# MiniDuino-v2.net
KiCad netlist of a schematic drawn in EAGLE
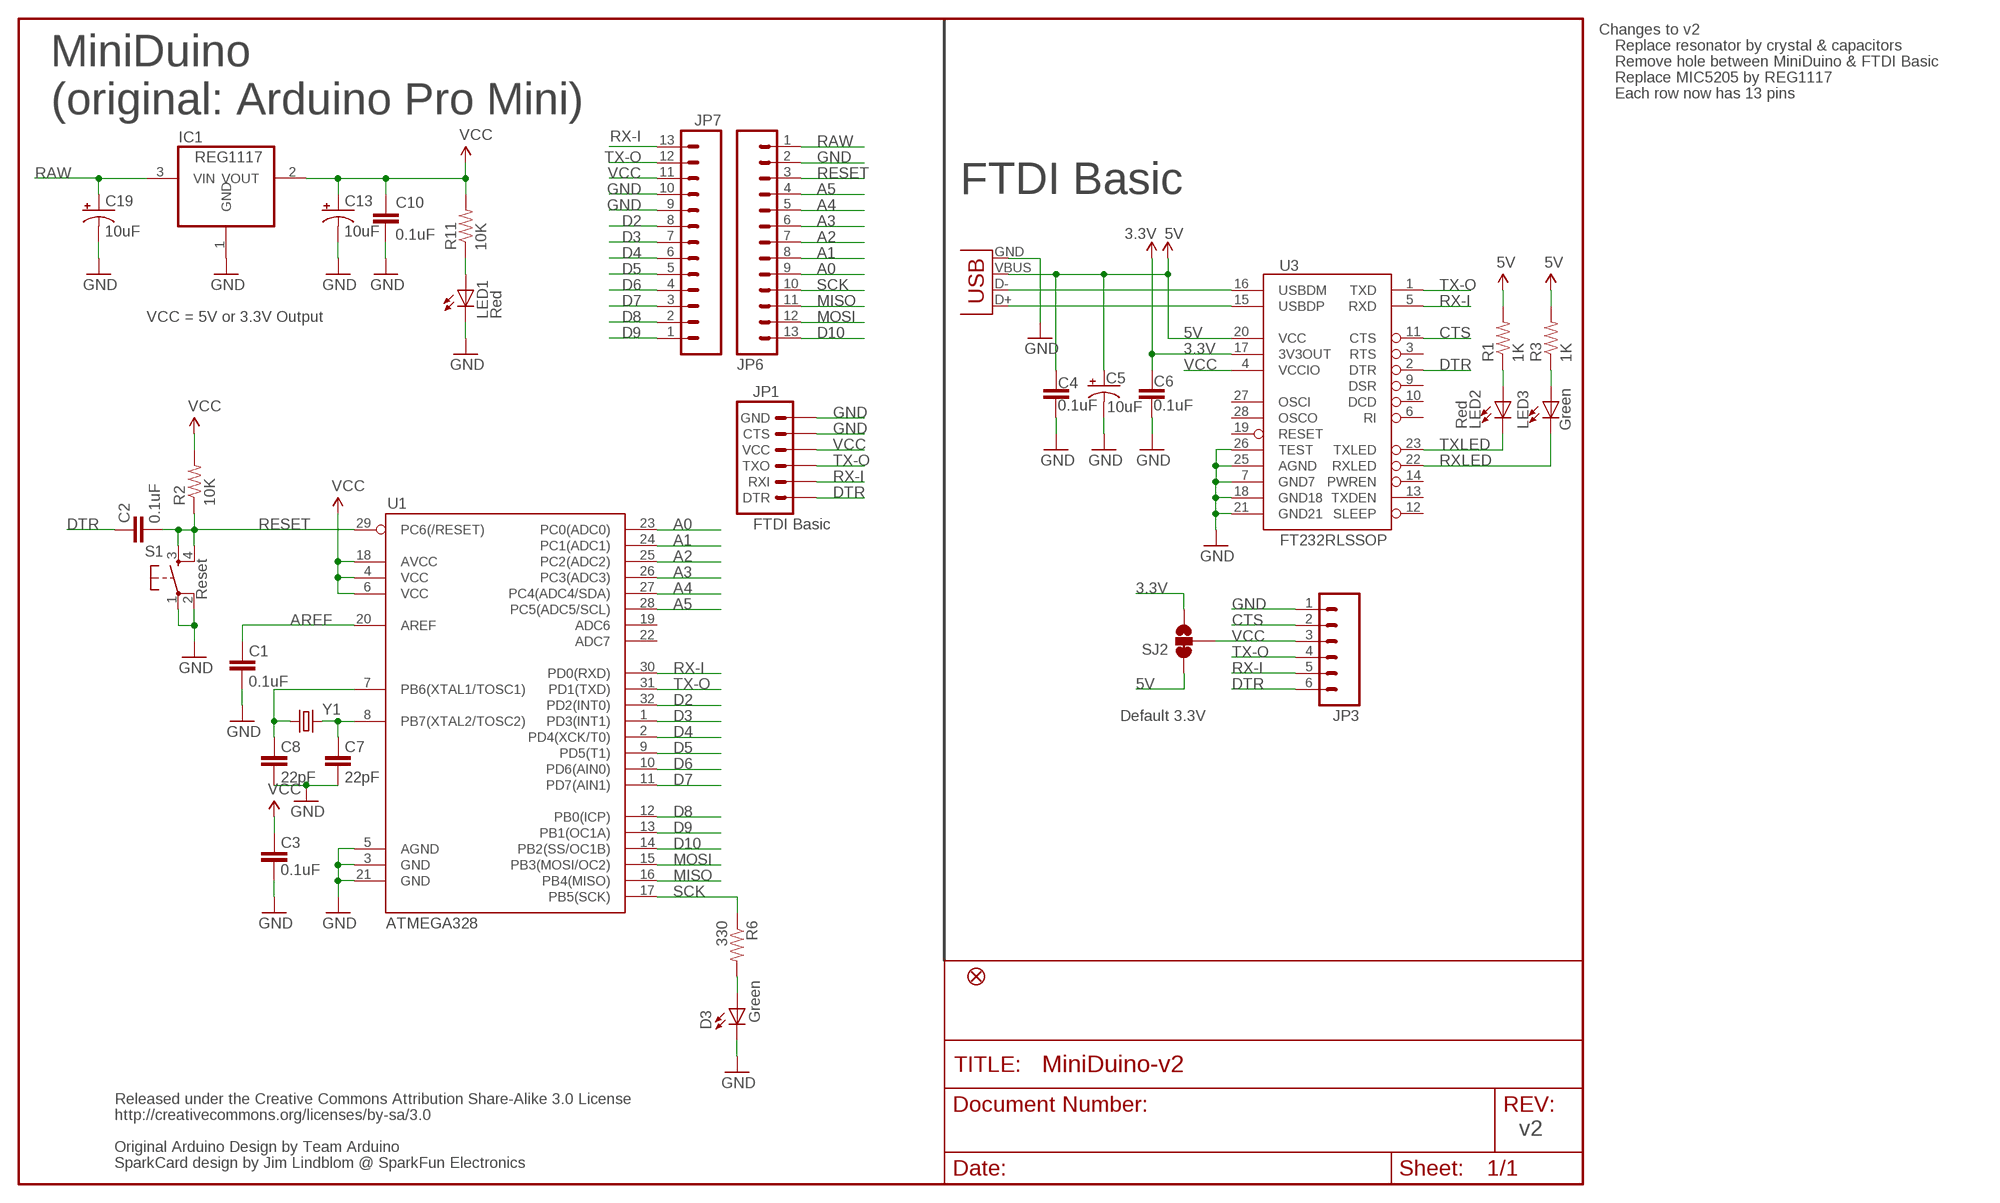
[diagram p0: schematic, sheet 1]

(export (version "E")
  (design (tool "Eeschema 10.0.6"))
  (components
    (comp (ref "C1")
      (value "0.1uF")
      (footprint "eagle-import:0402-CAP")
      (libsource (lib "eagle-import") (part "CAP0402-CAP"))
    )
    (comp (ref "C2")
      (value "0.1uF")
      (footprint "eagle-import:0402-CAP")
      (libsource (lib "eagle-import") (part "CAP0402-CAP"))
    )
    (comp (ref "C3")
      (value "0.1uF")
      (footprint "eagle-import:0402-CAP")
      (libsource (lib "eagle-import") (part "CAP0402-CAP"))
    )
    (comp (ref "C4")
      (value "0.1uF")
      (footprint "eagle-import:0402-CAP")
      (libsource (lib "eagle-import") (part "CAP0402-CAP"))
    )
    (comp (ref "C5")
      (value "10uF")
      (footprint "eagle-import:EIA3216")
      (libsource (lib "eagle-import") (part "CAP_POL1206"))
    )
    (comp (ref "C6")
      (value "0.1uF")
      (footprint "eagle-import:0402-CAP")
      (libsource (lib "eagle-import") (part "CAP0402-CAP"))
    )
    (comp (ref "C7")
      (value "22pF")
      (footprint "eagle-import:0402-CAP")
      (libsource (lib "eagle-import") (part "CAP0402-CAP"))
    )
    (comp (ref "C8")
      (value "22pF")
      (footprint "eagle-import:0402-CAP")
      (libsource (lib "eagle-import") (part "CAP0402-CAP"))
    )
    (comp (ref "C10")
      (value "0.1uF")
      (footprint "eagle-import:0402-CAP")
      (libsource (lib "eagle-import") (part "CAP0402-CAP"))
    )
    (comp (ref "C13")
      (value "10uF")
      (footprint "eagle-import:EIA3216")
      (libsource (lib "eagle-import") (part "CAP_POL1206"))
    )
    (comp (ref "C19")
      (value "10uF")
      (footprint "eagle-import:EIA3216")
      (libsource (lib "eagle-import") (part "CAP_POL1206"))
    )
    (comp (ref "D3")
      (value "Green")
      (footprint "eagle-import:LED-0603")
      (libsource (lib "eagle-import") (part "LED0603"))
    )
    (comp (ref "IC1")
      (value "REG1117")
      (footprint "eagle-import:SOT223")
      (libsource (lib "eagle-import") (part "REG1117"))
    )
    (comp (ref "JP1")
      (value "FTDI Basic")
      (footprint "eagle-import:1X06")
      (libsource (lib "eagle-import") (part "ARDUINO_SERIAL_PROGRAMPTH"))
    )
    (comp (ref "JP3")
      (value "M06SIP")
      (footprint "eagle-import:1X06")
      (libsource (lib "eagle-import") (part "M06SIP"))
    )
    (comp (ref "JP6")
      (value "M13")
      (footprint "eagle-import:1X13")
      (libsource (lib "eagle-import") (part "M13"))
    )
    (comp (ref "JP7")
      (value "M13")
      (footprint "eagle-import:1X13")
      (libsource (lib "eagle-import") (part "M13"))
    )
    (comp (ref "JP16")
      (value "FIDUCIAL1X2.5")
      (footprint "eagle-import:FIDUCIAL-1X2.5")
      (libsource (lib "eagle-import") (part "FIDUCIAL1X2.5"))
    )
    (comp (ref "LED1")
      (value "Red")
      (footprint "eagle-import:LED-0603")
      (libsource (lib "eagle-import") (part "LED0603"))
    )
    (comp (ref "LED2")
      (value "Red")
      (footprint "eagle-import:LED-0603")
      (libsource (lib "eagle-import") (part "LED0603"))
    )
    (comp (ref "LED3")
      (value "Green")
      (footprint "eagle-import:LED-0603")
      (libsource (lib "eagle-import") (part "LED0603"))
    )
    (comp (ref "R1")
      (value "1K")
      (footprint "eagle-import:0603-RES")
      (libsource (lib "eagle-import") (part "RESISTOR0603-RES"))
    )
    (comp (ref "R2")
      (value "10K")
      (footprint "eagle-import:0402-RES")
      (libsource (lib "eagle-import") (part "RESISTOR0402-RES"))
    )
    (comp (ref "R3")
      (value "1K")
      (footprint "eagle-import:0603-RES")
      (libsource (lib "eagle-import") (part "RESISTOR0603-RES"))
    )
    (comp (ref "R6")
      (value "330")
      (footprint "eagle-import:0402-RES")
      (libsource (lib "eagle-import") (part "RESISTOR0402-RES"))
    )
    (comp (ref "R11")
      (value "10K")
      (footprint "eagle-import:0402-RES")
      (libsource (lib "eagle-import") (part "RESISTOR0402-RES"))
    )
    (comp (ref "S1")
      (value "Reset")
      (footprint "eagle-import:TACTILE_SWITCH_SMD")
      (libsource (lib "eagle-import") (part "TAC_SWITCHSMD"))
    )
    (comp (ref "SJ2")
      (value "SOLDERJUMPER_2WAYS")
      (footprint "eagle-import:SJ_3")
      (libsource (lib "eagle-import") (part "SOLDERJUMPER_2WAYS"))
    )
    (comp (ref "U1")
      (value "ATMEGA328")
      (footprint "eagle-import:TQFP32-08")
      (libsource (lib "eagle-import") (part "ATMEGA168"))
    )
    (comp (ref "U3")
      (value "FT232RLSSOP")
      (footprint "eagle-import:SSOP28DB")
      (libsource (lib "eagle-import") (part "FT232RLSSOP"))
    )
    (comp (ref "X2")
      (value "USB-SMD-NS")
      (footprint "eagle-import:USB-MINIB-NOSTOP")
      (libsource (lib "eagle-import") (part "USB-SMD-NS"))
    )
    (comp (ref "Y1")
      (value "CRYSTAL5X3")
      (footprint "eagle-import:CRYSTAL-SMD-5X3")
      (libsource (lib "eagle-import") (part "CRYSTAL5X3"))
    )
  )
  (nets
    (net (code "1") (name "/A0") (class "Default")
      (node (ref "JP6") (pin "9") (pinfunction "9_9") (pintype "passive"))
      (node (ref "U1") (pin "23") (pinfunction "PC0(ADC0)_23") (pintype "bidirectional"))
    )
    (net (code "2") (name "/A1") (class "Default")
      (node (ref "JP6") (pin "8") (pinfunction "8_8") (pintype "passive"))
      (node (ref "U1") (pin "24") (pinfunction "PC1(ADC1)_24") (pintype "bidirectional"))
    )
    (net (code "3") (name "/A2") (class "Default")
      (node (ref "JP6") (pin "7") (pinfunction "7_7") (pintype "passive"))
      (node (ref "U1") (pin "25") (pinfunction "PC2(ADC2)_25") (pintype "bidirectional"))
    )
    (net (code "4") (name "/A3") (class "Default")
      (node (ref "JP6") (pin "6") (pinfunction "6_6") (pintype "passive"))
      (node (ref "U1") (pin "26") (pinfunction "PC3(ADC3)_26") (pintype "bidirectional"))
    )
    (net (code "5") (name "/A4") (class "Default")
      (node (ref "JP6") (pin "5") (pinfunction "5_5") (pintype "passive"))
      (node (ref "U1") (pin "27") (pinfunction "PC4(ADC4/SDA)_27") (pintype "bidirectional"))
    )
    (net (code "6") (name "/A5") (class "Default")
      (node (ref "JP6") (pin "4") (pinfunction "4_4") (pintype "passive"))
      (node (ref "U1") (pin "28") (pinfunction "PC5(ADC5/SCL)_28") (pintype "bidirectional"))
    )
    (net (code "7") (name "/AREF") (class "Default")
      (node (ref "C1") (pin "2") (pinfunction "2_2") (pintype "passive"))
      (node (ref "U1") (pin "20") (pinfunction "AREF_20") (pintype "bidirectional"))
    )
    (net (code "8") (name "/CTS") (class "Default")
      (node (ref "JP3") (pin "2") (pinfunction "2_2") (pintype "passive"))
      (node (ref "U3") (pin "11") (pinfunction "CTS_11") (pintype "input"))
    )
    (net (code "9") (name "/D2") (class "Default")
      (node (ref "JP7") (pin "8") (pinfunction "8_8") (pintype "passive"))
      (node (ref "U1") (pin "32") (pinfunction "PD2(INT0)_32") (pintype "bidirectional"))
    )
    (net (code "10") (name "/D3") (class "Default")
      (node (ref "JP7") (pin "7") (pinfunction "7_7") (pintype "passive"))
      (node (ref "U1") (pin "1") (pinfunction "PD3(INT1)_1") (pintype "bidirectional"))
    )
    (net (code "11") (name "/D4") (class "Default")
      (node (ref "JP7") (pin "6") (pinfunction "6_6") (pintype "passive"))
      (node (ref "U1") (pin "2") (pinfunction "PD4(XCK/T0)_2") (pintype "bidirectional"))
    )
    (net (code "12") (name "/D5") (class "Default")
      (node (ref "JP7") (pin "5") (pinfunction "5_5") (pintype "passive"))
      (node (ref "U1") (pin "9") (pinfunction "PD5(T1)_9") (pintype "bidirectional"))
    )
    (net (code "13") (name "/D6") (class "Default")
      (node (ref "JP7") (pin "4") (pinfunction "4_4") (pintype "passive"))
      (node (ref "U1") (pin "10") (pinfunction "PD6(AIN0)_10") (pintype "bidirectional"))
    )
    (net (code "14") (name "/D7") (class "Default")
      (node (ref "JP7") (pin "3") (pinfunction "3_3") (pintype "passive"))
      (node (ref "U1") (pin "11") (pinfunction "PD7(AIN1)_11") (pintype "bidirectional"))
    )
    (net (code "15") (name "/D8") (class "Default")
      (node (ref "JP7") (pin "2") (pinfunction "2_2") (pintype "passive"))
      (node (ref "U1") (pin "12") (pinfunction "PB0(ICP)_12") (pintype "bidirectional"))
    )
    (net (code "16") (name "/D9") (class "Default")
      (node (ref "JP7") (pin "1") (pinfunction "1_1") (pintype "passive"))
      (node (ref "U1") (pin "13") (pinfunction "PB1(OC1A)_13") (pintype "bidirectional"))
    )
    (net (code "17") (name "/D10") (class "Default")
      (node (ref "JP6") (pin "13") (pinfunction "13_13") (pintype "passive"))
      (node (ref "U1") (pin "14") (pinfunction "PB2(SS/OC1B)_14") (pintype "bidirectional"))
    )
    (net (code "18") (name "/DTR") (class "Default")
      (node (ref "C2") (pin "2") (pinfunction "2_2") (pintype "passive"))
      (node (ref "JP1") (pin "1") (pinfunction "DTR_1") (pintype "passive"))
      (node (ref "JP3") (pin "6") (pinfunction "6_6") (pintype "passive"))
      (node (ref "U3") (pin "2") (pinfunction "DTR_2") (pintype "output"))
    )
    (net (code "19") (name "/MISO") (class "Default")
      (node (ref "JP6") (pin "11") (pinfunction "11_11") (pintype "passive"))
      (node (ref "U1") (pin "16") (pinfunction "PB4(MISO)_16") (pintype "bidirectional"))
    )
    (net (code "20") (name "/MOSI") (class "Default")
      (node (ref "JP6") (pin "12") (pinfunction "12_12") (pintype "passive"))
      (node (ref "U1") (pin "15") (pinfunction "PB3(MOSI/OC2)_15") (pintype "bidirectional"))
    )
    (net (code "21") (name "/RAW") (class "Default")
      (node (ref "C19") (pin "A") (pinfunction "+_A") (pintype "passive"))
      (node (ref "IC1") (pin "3") (pinfunction "VIN_3") (pintype "input"))
      (node (ref "JP6") (pin "1") (pinfunction "1_1") (pintype "passive"))
    )
    (net (code "22") (name "/RESET") (class "Default")
      (node (ref "C2") (pin "1") (pinfunction "1_1") (pintype "passive"))
      (node (ref "JP6") (pin "3") (pinfunction "3_3") (pintype "passive"))
      (node (ref "R2") (pin "1") (pinfunction "1_1") (pintype "passive"))
      (node (ref "S1") (pin "3") (pinfunction "3_3") (pintype "passive"))
      (node (ref "S1") (pin "4") (pinfunction "4_4") (pintype "passive"))
      (node (ref "U1") (pin "29") (pinfunction "PC6(/RESET)_29") (pintype "bidirectional"))
    )
    (net (code "23") (name "/RX-I") (class "Default")
      (node (ref "JP1") (pin "2") (pinfunction "RXI_2") (pintype "passive"))
      (node (ref "JP3") (pin "5") (pinfunction "5_5") (pintype "passive"))
      (node (ref "JP7") (pin "13") (pinfunction "13_13") (pintype "passive"))
      (node (ref "U1") (pin "30") (pinfunction "PD0(RXD)_30") (pintype "bidirectional"))
      (node (ref "U3") (pin "5") (pinfunction "RXD_5") (pintype "input"))
    )
    (net (code "24") (name "/RXLED") (class "Default")
      (node (ref "LED3") (pin "C") (pinfunction "C_C") (pintype "passive"))
      (node (ref "U3") (pin "22") (pinfunction "RXLED_22") (pintype "input"))
    )
    (net (code "25") (name "/SCK") (class "Default")
      (node (ref "JP6") (pin "10") (pinfunction "10_10") (pintype "passive"))
      (node (ref "R6") (pin "1") (pinfunction "1_1") (pintype "passive"))
      (node (ref "U1") (pin "17") (pinfunction "PB5(SCK)_17") (pintype "bidirectional"))
    )
    (net (code "26") (name "/TX-O") (class "Default")
      (node (ref "JP1") (pin "3") (pinfunction "TXO_3") (pintype "passive"))
      (node (ref "JP3") (pin "4") (pinfunction "4_4") (pintype "passive"))
      (node (ref "JP7") (pin "12") (pinfunction "12_12") (pintype "passive"))
      (node (ref "U1") (pin "31") (pinfunction "PD1(TXD)_31") (pintype "bidirectional"))
      (node (ref "U3") (pin "1") (pinfunction "TXD_1") (pintype "output"))
    )
    (net (code "27") (name "/TXLED") (class "Default")
      (node (ref "LED2") (pin "C") (pinfunction "C_C") (pintype "passive"))
      (node (ref "U3") (pin "23") (pinfunction "TXLED_23") (pintype "input"))
    )
    (net (code "28") (name "3.3V") (class "Default")
      (node (ref "C6") (pin "1") (pinfunction "1_1") (pintype "passive"))
      (node (ref "SJ2") (pin "3") (pinfunction "3_3") (pintype "passive"))
      (node (ref "U3") (pin "17") (pinfunction "3V3OUT_17") (pintype "output"))
    )
    (net (code "29") (name "5V") (class "Default")
      (node (ref "C4") (pin "1") (pinfunction "1_1") (pintype "passive"))
      (node (ref "C5") (pin "A") (pinfunction "+_A") (pintype "passive"))
      (node (ref "R1") (pin "2") (pinfunction "2_2") (pintype "passive"))
      (node (ref "R3") (pin "2") (pinfunction "2_2") (pintype "passive"))
      (node (ref "SJ2") (pin "1") (pinfunction "1_1") (pintype "passive"))
      (node (ref "U3") (pin "20") (pinfunction "VCC_20") (pintype "power_in"))
      (node (ref "X2") (pin "VBUS") (pinfunction "VBUS_VBUS") (pintype "bidirectional"))
    )
    (net (code "30") (name "GND") (class "Default")
      (node (ref "C1") (pin "1") (pinfunction "1_1") (pintype "passive"))
      (node (ref "C10") (pin "2") (pinfunction "2_2") (pintype "passive"))
      (node (ref "C13") (pin "C") (pinfunction "-_C") (pintype "passive"))
      (node (ref "C19") (pin "C") (pinfunction "-_C") (pintype "passive"))
      (node (ref "C3") (pin "1") (pinfunction "1_1") (pintype "passive"))
      (node (ref "C4") (pin "2") (pinfunction "2_2") (pintype "passive"))
      (node (ref "C5") (pin "C") (pinfunction "-_C") (pintype "passive"))
      (node (ref "C6") (pin "2") (pinfunction "2_2") (pintype "passive"))
      (node (ref "C7") (pin "1") (pinfunction "1_1") (pintype "passive"))
      (node (ref "C8") (pin "1") (pinfunction "1_1") (pintype "passive"))
      (node (ref "D3") (pin "C") (pinfunction "C_C") (pintype "passive"))
      (node (ref "IC1") (pin "1") (pinfunction "GND_1") (pintype "power_in"))
      (node (ref "JP1") (pin "5") (pinfunction "CTS_5") (pintype "passive"))
      (node (ref "JP1") (pin "6") (pinfunction "GND_6") (pintype "passive"))
      (node (ref "JP3") (pin "1") (pinfunction "1_1") (pintype "passive"))
      (node (ref "JP6") (pin "2") (pinfunction "2_2") (pintype "passive"))
      (node (ref "JP7") (pin "10") (pinfunction "10_10") (pintype "passive"))
      (node (ref "JP7") (pin "9") (pinfunction "9_9") (pintype "passive"))
      (node (ref "LED1") (pin "C") (pinfunction "C_C") (pintype "passive"))
      (node (ref "S1") (pin "1") (pinfunction "1_1") (pintype "passive"))
      (node (ref "S1") (pin "2") (pinfunction "2_2") (pintype "passive"))
      (node (ref "U1") (pin "21") (pinfunction "GND_21") (pintype "bidirectional"))
      (node (ref "U1") (pin "3") (pinfunction "GND_3") (pintype "bidirectional"))
      (node (ref "U1") (pin "5") (pinfunction "AGND_5") (pintype "bidirectional"))
      (node (ref "U3") (pin "18") (pinfunction "GND18_18") (pintype "power_in"))
      (node (ref "U3") (pin "21") (pinfunction "GND21_21") (pintype "power_in"))
      (node (ref "U3") (pin "25") (pinfunction "AGND_25") (pintype "power_in"))
      (node (ref "U3") (pin "26") (pinfunction "TEST_26") (pintype "input"))
      (node (ref "U3") (pin "7") (pinfunction "GND7_7") (pintype "power_in"))
      (node (ref "X2") (pin "GND") (pinfunction "GND_GND") (pintype "bidirectional"))
    )
    (net (code "31") (name "Net-(D3-PadA)") (class "Default")
      (node (ref "D3") (pin "A") (pinfunction "A_A") (pintype "passive"))
      (node (ref "R6") (pin "2") (pinfunction "2_2") (pintype "passive"))
    )
    (net (code "32") (name "Net-(LED1-PadA)") (class "Default")
      (node (ref "LED1") (pin "A") (pinfunction "A_A") (pintype "passive"))
      (node (ref "R11") (pin "1") (pinfunction "1_1") (pintype "passive"))
    )
    (net (code "33") (name "Net-(LED2-PadA)") (class "Default")
      (node (ref "LED2") (pin "A") (pinfunction "A_A") (pintype "passive"))
      (node (ref "R1") (pin "1") (pinfunction "1_1") (pintype "passive"))
    )
    (net (code "34") (name "Net-(LED3-PadA)") (class "Default")
      (node (ref "LED3") (pin "A") (pinfunction "A_A") (pintype "passive"))
      (node (ref "R3") (pin "1") (pinfunction "1_1") (pintype "passive"))
    )
    (net (code "35") (name "Net-(U1-PB6(XTAL1{slash}TOSC1))") (class "Default")
      (node (ref "C8") (pin "2") (pinfunction "2_2") (pintype "passive"))
      (node (ref "U1") (pin "7") (pinfunction "PB6(XTAL1/TOSC1)_7") (pintype "bidirectional"))
      (node (ref "Y1") (pin "1") (pinfunction "1_1") (pintype "passive"))
    )
    (net (code "36") (name "Net-(U1-PB7(XTAL2{slash}TOSC2))") (class "Default")
      (node (ref "C7") (pin "2") (pinfunction "2_2") (pintype "passive"))
      (node (ref "U1") (pin "8") (pinfunction "PB7(XTAL2/TOSC2)_8") (pintype "bidirectional"))
      (node (ref "Y1") (pin "3") (pinfunction "2_3") (pintype "passive"))
    )
    (net (code "37") (name "Net-(U3-USBDM)") (class "Default")
      (node (ref "U3") (pin "16") (pinfunction "USBDM_16") (pintype "bidirectional"))
      (node (ref "X2") (pin "D-") (pinfunction "D-_D-") (pintype "bidirectional"))
    )
    (net (code "38") (name "Net-(U3-USBDP)") (class "Default")
      (node (ref "U3") (pin "15") (pinfunction "USBDP_15") (pintype "bidirectional"))
      (node (ref "X2") (pin "D+") (pinfunction "D+_D+") (pintype "bidirectional"))
    )
    (net (code "39") (name "VCC") (class "Default")
      (node (ref "C10") (pin "1") (pinfunction "1_1") (pintype "passive"))
      (node (ref "C13") (pin "A") (pinfunction "+_A") (pintype "passive"))
      (node (ref "C3") (pin "2") (pinfunction "2_2") (pintype "passive"))
      (node (ref "IC1") (pin "2") (pinfunction "VOUT_2") (pintype "output"))
      (node (ref "JP1") (pin "4") (pinfunction "VCC_4") (pintype "passive"))
      (node (ref "JP3") (pin "3") (pinfunction "3_3") (pintype "passive"))
      (node (ref "JP7") (pin "11") (pinfunction "11_11") (pintype "passive"))
      (node (ref "R11") (pin "2") (pinfunction "2_2") (pintype "passive"))
      (node (ref "R2") (pin "2") (pinfunction "2_2") (pintype "passive"))
      (node (ref "SJ2") (pin "2") (pinfunction "2_2") (pintype "passive"))
      (node (ref "U1") (pin "18") (pinfunction "AVCC_18") (pintype "bidirectional"))
      (node (ref "U1") (pin "4") (pinfunction "VCC_4") (pintype "bidirectional"))
      (node (ref "U1") (pin "6") (pinfunction "VCC_6") (pintype "bidirectional"))
      (node (ref "U3") (pin "4") (pinfunction "VCCIO_4") (pintype "power_in"))
    )
    (net (code "40") (name "unconnected-(U1-ADC6-Pad19)") (class "Default")
      (node (ref "U1") (pin "19") (pinfunction "ADC6_19") (pintype "bidirectional"))
    )
    (net (code "41") (name "unconnected-(U1-ADC7-Pad22)") (class "Default")
      (node (ref "U1") (pin "22") (pinfunction "ADC7_22") (pintype "bidirectional"))
    )
    (net (code "42") (name "unconnected-(U3-DCD-Pad10)") (class "Default")
      (node (ref "U3") (pin "10") (pinfunction "DCD_10") (pintype "input"))
    )
    (net (code "43") (name "unconnected-(U3-DSR-Pad9)") (class "Default")
      (node (ref "U3") (pin "9") (pinfunction "DSR_9") (pintype "input"))
    )
    (net (code "44") (name "unconnected-(U3-OSCI-Pad27)") (class "Default")
      (node (ref "U3") (pin "27") (pinfunction "OSCI_27") (pintype "input"))
    )
    (net (code "45") (name "unconnected-(U3-OSCO-Pad28)") (class "Default")
      (node (ref "U3") (pin "28") (pinfunction "OSCO_28") (pintype "output"))
    )
    (net (code "46") (name "unconnected-(U3-PWREN-Pad14)") (class "Default")
      (node (ref "U3") (pin "14") (pinfunction "PWREN_14") (pintype "input"))
    )
    (net (code "47") (name "unconnected-(U3-RESET-Pad19)") (class "Default")
      (node (ref "U3") (pin "19") (pinfunction "RESET_19") (pintype "input"))
    )
    (net (code "48") (name "unconnected-(U3-RI-Pad6)") (class "Default")
      (node (ref "U3") (pin "6") (pinfunction "RI_6") (pintype "input"))
    )
    (net (code "49") (name "unconnected-(U3-RTS-Pad3)") (class "Default")
      (node (ref "U3") (pin "3") (pinfunction "RTS_3") (pintype "output"))
    )
    (net (code "50") (name "unconnected-(U3-SLEEP-Pad12)") (class "Default")
      (node (ref "U3") (pin "12") (pinfunction "SLEEP_12") (pintype "input"))
    )
    (net (code "51") (name "unconnected-(U3-TXDEN-Pad13)") (class "Default")
      (node (ref "U3") (pin "13") (pinfunction "TXDEN_13") (pintype "input"))
    )
  )
)
